# PWM_To_Analog_RSSI_v1_0.net
KiCad netlist of a schematic drawn in EAGLE
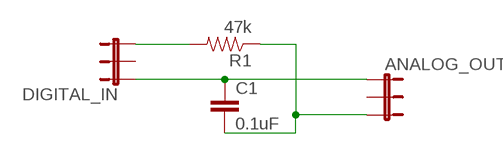
[diagram p0: schematic, sheet 1]

(export (version "E")
  (design (tool "Eeschema 10.0.6"))
  (components
    (comp (ref "ANALOG_OUT")
      (value "JUMPER-3PTH")
      (footprint "eagle-import:1X03")
      (libsource (lib "eagle-import") (part "JUMPER-3PTH"))
    )
    (comp (ref "C1")
      (value "0.1uF")
      (footprint "eagle-import:CAP-PTH-SMALL")
      (libsource (lib "eagle-import") (part "CAPPTH"))
    )
    (comp (ref "DIGITAL_IN")
      (value "JUMPER-3PTH")
      (footprint "eagle-import:1X03")
      (libsource (lib "eagle-import") (part "JUMPER-3PTH"))
    )
    (comp (ref "R1")
      (value "47k")
      (footprint "eagle-import:AXIAL-0.3-KIT")
      (libsource (lib "eagle-import") (part "RESISTORKIT"))
    )
  )
  (nets
    (net (code "1") (name "Net-(ANALOG_OUT-Pad1)") (class "Default")
      (node (ref "ANALOG_OUT") (pin "1") (pinfunction "1_1") (pintype "passive"))
      (node (ref "C1") (pin "1") (pinfunction "1_1") (pintype "passive"))
      (node (ref "DIGITAL_IN") (pin "1") (pinfunction "1_1") (pintype "passive"))
    )
    (net (code "2") (name "Net-(R1-1)") (class "Default")
      (node (ref "ANALOG_OUT") (pin "3") (pinfunction "3_3") (pintype "passive"))
      (node (ref "C1") (pin "2") (pinfunction "2_2") (pintype "passive"))
      (node (ref "R1") (pin "P$1") (pinfunction "1_P$1") (pintype "passive"))
    )
    (net (code "3") (name "Net-(R1-2)") (class "Default")
      (node (ref "DIGITAL_IN") (pin "3") (pinfunction "3_3") (pintype "passive"))
      (node (ref "R1") (pin "P$2") (pinfunction "2_P$2") (pintype "passive"))
    )
    (net (code "4") (name "unconnected-(ANALOG_OUT-Pad2)") (class "Default")
      (node (ref "ANALOG_OUT") (pin "2") (pinfunction "2_2") (pintype "passive"))
    )
    (net (code "5") (name "unconnected-(DIGITAL_IN-Pad2)") (class "Default")
      (node (ref "DIGITAL_IN") (pin "2") (pinfunction "2_2") (pintype "passive"))
    )
  )
)
